# updated_sami_board.net
KiCad netlist of a schematic drawn in Altium Designer
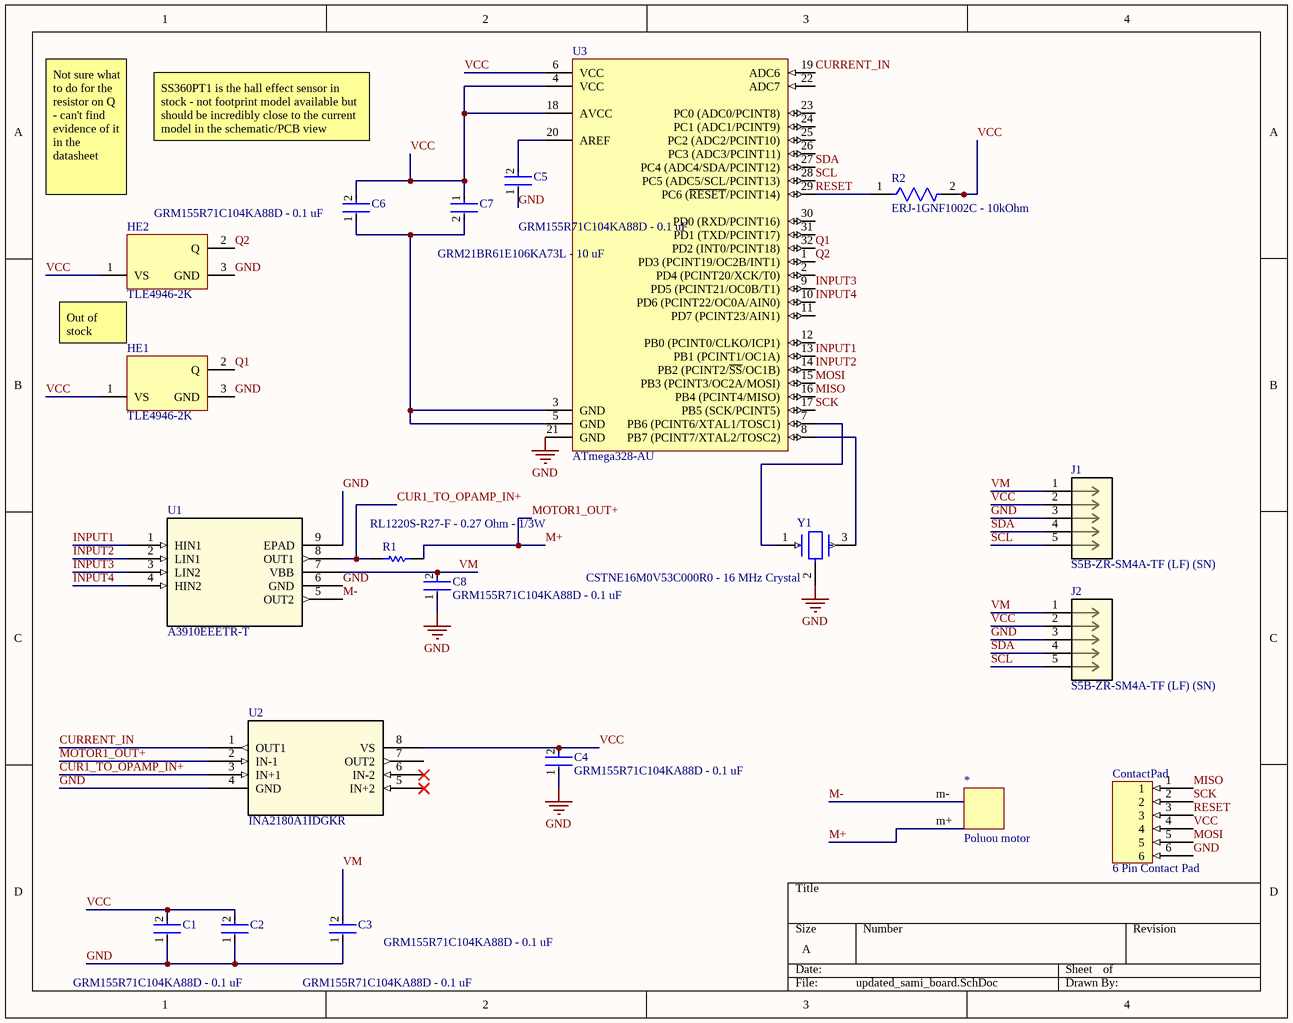
[diagram p0: updated_sami_board.SchDoc]

(export (version "E")
  (design (tool "Eeschema 10.0.6"))
  (components
    (comp (ref "*")
      (value "Poluou motor")
      (footprint "PCBComponent_1")
      (libsource (lib "polulu_motor") (part "Poluou motor"))
    )
    (comp (ref "C1")
      (value "GRM155R71C104KA88D - 0.1 uF")
      (footprint "FP-GRM15-MFG")
      (description "CAP CER 0.1UF 16V X7R 0402")
      (fields (field (name "MANUFACTURER PART NUMBER") "GRM155R71C104KA88D") (field (name "TOLERANCE") "10%"))
      (libsource (lib "Altium Content Vault") (part "236180d848d6139a670b325ea6854c9"))
    )
    (comp (ref "C2")
      (value "GRM155R71C104KA88D - 0.1 uF")
      (footprint "FP-GRM15-MFG")
      (description "CAP CER 0.1UF 16V X7R 0402")
      (fields (field (name "MANUFACTURER PART NUMBER") "GRM155R71C104KA88D") (field (name "TOLERANCE") "10%"))
      (libsource (lib "Altium Content Vault") (part "236180d848d6139a670b325ea6854c9"))
    )
    (comp (ref "C3")
      (value "GRM155R71C104KA88D - 0.1 uF")
      (footprint "FP-GRM15-MFG")
      (description "CAP CER 0.1UF 16V X7R 0402")
      (fields (field (name "MANUFACTURER PART NUMBER") "GRM155R71C104KA88D") (field (name "TOLERANCE") "10%"))
      (libsource (lib "Altium Content Vault") (part "236180d848d6139a670b325ea6854c9"))
    )
    (comp (ref "C4")
      (value "GRM155R71C104KA88D - 0.1 uF")
      (footprint "FP-GRM15-MFG")
      (description "CAP CER 0.1UF 16V X7R 0402")
      (fields (field (name "MANUFACTURER PART NUMBER") "GRM155R71C104KA88D") (field (name "TOLERANCE") "10%"))
      (libsource (lib "Altium Content Vault") (part "236180d848d6139a670b325ea6854c9"))
    )
    (comp (ref "C5")
      (value "GRM155R71C104KA88D - 0.1 uF")
      (footprint "FP-GRM15-MFG")
      (description "CAP CER 0.1UF 16V X7R 0402")
      (fields (field (name "MANUFACTURER PART NUMBER") "GRM155R71C104KA88D") (field (name "TOLERANCE") "10%"))
      (libsource (lib "Altium Content Vault") (part "236180d848d6139a670b325ea6854c9"))
    )
    (comp (ref "C6")
      (value "GRM155R71C104KA88D - 0.1 uF")
      (footprint "FP-GRM15-MFG")
      (description "CAP CER 0.1UF 16V X7R 0402")
      (fields (field (name "MANUFACTURER PART NUMBER") "GRM155R71C104KA88D") (field (name "TOLERANCE") "10%"))
      (libsource (lib "Altium Content Vault") (part "236180d848d6139a670b325ea6854c9"))
    )
    (comp (ref "C7")
      (value "GRM21BR61E106KA73L - 10 uF")
      (footprint "FP-GRM21B-0_15-IPC_C")
      (description "Chip Multilayer Ceramic Capacitors for General Purpose, 0805, 10uF, X5R, 15%, 10%, 25V")
      (fields (field (name "VOLTAGE") "25V") (field (name "TOLERANCE") "10%"))
      (libsource (lib "Altium Content Vault") (part "b4654b650e69147ec39a6b967a45e02"))
    )
    (comp (ref "C8")
      (value "GRM155R71C104KA88D - 0.1 uF")
      (footprint "FP-GRM15-MFG")
      (description "CAP CER 0.1UF 16V X7R 0402")
      (fields (field (name "MANUFACTURER PART NUMBER") "GRM155R71C104KA88D") (field (name "TOLERANCE") "10%"))
      (libsource (lib "Altium Content Vault") (part "236180d848d6139a670b325ea6854c9"))
    )
    (comp (ref "ContactPad")
      (value "6 Pin Contact Pad")
      (footprint "6PinContactPad")
      (libsource (lib "6PinContactPad") (part "6 Pin Contact Pad"))
    )
    (comp (ref "HE1")
      (value "TLE4946-2K")
      (footprint "INF-PG-SC59_M")
      (description "High Precision Hall Effect Latch, PG-SC59, Reel, Green")
      (fields (field (name "MANUFACTURER") "Infineon"))
      (libsource (lib "Altium Content Vault") (part "INF-TLE49XX-SC59-3"))
    )
    (comp (ref "HE2")
      (value "TLE4946-2K")
      (footprint "INF-PG-SC59_M")
      (description "High Precision Hall Effect Latch, PG-SC59, Reel, Green")
      (fields (field (name "MANUFACTURER") "Infineon"))
      (libsource (lib "Altium Content Vault") (part "INF-TLE49XX-SC59-3"))
    )
    (comp (ref "J1")
      (value "S5B-ZR-SM4A-TF (LF) (SN)")
      (footprint "CONN_S5B-ZR-SM4A-TF_JST")
      (description "No Description Available")
      (fields (field (name "COPYRIGHT") "Copyright (C) 2021 Ultra Librarian. All rights reserved."))
      (libsource (lib "S5B-ZR-SM4A-TF_LF__SN_") (part "S5B-ZR-SM4A-TF (LF) (SN)"))
    )
    (comp (ref "J2")
      (value "S5B-ZR-SM4A-TF (LF) (SN)")
      (footprint "CONN_S5B-ZR-SM4A-TF_JST")
      (description "No Description Available")
      (fields (field (name "COPYRIGHT") "Copyright (C) 2021 Ultra Librarian. All rights reserved."))
      (libsource (lib "S5B-ZR-SM4A-TF_LF__SN_") (part "S5B-ZR-SM4A-TF (LF) (SN)"))
    )
    (comp (ref "R1")
      (value "RL1220S-R27-F - 0.27 Ohm - 1/3W")
      (footprint "RESC2013X50X40NL20T20")
      (fields (field (name "PART NUMBER") "RL1220S-R27-F") (field (name "MANUFACTURER") "Susumu"))
      (libsource (lib "Altium Content Vault") (part "RES"))
    )
    (comp (ref "R2")
      (value "ERJ-1GNF1002C - 10kOhm")
      (footprint "FP-ERJ1G-MFG")
      (description "RES SMD 10K OHM 1% 1/20W 0201")
      (fields
        (field (name "MANUFACTURER PART NUMBER") "ERJ-1GNF1002C")
        (field (name "OCTOPART") "https://octopart.com/erj-1gnf1002c-panasonic-55419697")
      )
      (libsource (lib "Altium Content Vault") (part "1029c3af85768c4190bb7ad29bc67b5"))
    )
    (comp (ref "U1")
      (value "A3910EEETR-T")
      (footprint "DFN-8_ALM")
      (description "No Description Available")
      (fields (field (name "COPYRIGHT") "Copyright (C) 2021 Ultra Librarian. All rights reserved."))
      (libsource (lib "A3910EEETR-T") (part "A3910EEETR-T"))
    )
    (comp (ref "U2")
      (value "INA2180A1IDGKR")
      (footprint "DGK8_TEX")
      (description "No Description Available")
      (fields (field (name "COPYRIGHT") "Copyright (C) 2021 Ultra Librarian. All rights reserved."))
      (libsource (lib "INA2180A1IDGKR") (part "INA2180A1IDGKR"))
    )
    (comp (ref "U3")
      (value "ATmega328-AU")
      (footprint "32A_L")
      (libsource (lib "Altium Content Vault") (part "MC-8B-ATM48-SQ32"))
    )
    (comp (ref "Y1")
      (value "CSTNE16M0V53C000R0 - 16 MHz Crystal")
      (footprint "FP-CSTNE16M0V53C000R0-MFG")
      (description "CERAMIC RES 16.0000MHZ 15PF SMD")
      (libsource (lib "Altium Content Vault") (part "7d37667f5012bb31280c8009ddd0b1c"))
    )
  )
  (nets
    (net (code "1") (name "/CUR1_TO_OPAMP_IN+") (class "Default")
      (node (ref "R1") (pin "1") (pinfunction "1_1") (pintype "passive"))
      (node (ref "U1") (pin "8") (pinfunction "OUT1_8") (pintype "output"))
      (node (ref "U2") (pin "3") (pinfunction "IN+1_3") (pintype "input"))
    )
    (net (code "2") (name "/CURRENT_IN") (class "Default")
      (node (ref "U2") (pin "1") (pinfunction "OUT1_1") (pintype "output"))
      (node (ref "U3") (pin "19") (pinfunction "ADC6_19") (pintype "input"))
    )
    (net (code "3") (name "/INPUT1") (class "Default")
      (node (ref "U1") (pin "1") (pinfunction "HIN1_1") (pintype "input"))
      (node (ref "U3") (pin "13") (pinfunction "PB1_(PCINT1/OC1A)_13") (pintype "bidirectional"))
    )
    (net (code "4") (name "/INPUT2") (class "Default")
      (node (ref "U1") (pin "2") (pinfunction "LIN1_2") (pintype "input"))
      (node (ref "U3") (pin "14") (pinfunction "PB2_(PCINT2/~{SS}/OC1B)_14") (pintype "bidirectional"))
    )
    (net (code "5") (name "/INPUT3") (class "Default")
      (node (ref "U1") (pin "3") (pinfunction "LIN2_3") (pintype "input"))
      (node (ref "U3") (pin "9") (pinfunction "PD5_(PCINT21/OC0B/T1)_9") (pintype "bidirectional"))
    )
    (net (code "6") (name "/INPUT4") (class "Default")
      (node (ref "U1") (pin "4") (pinfunction "HIN2_4") (pintype "input"))
      (node (ref "U3") (pin "10") (pinfunction "PD6_(PCINT22/OC0A/AIN0)_10") (pintype "bidirectional"))
    )
    (net (code "7") (name "/M+") (class "Default")
      (node (ref "*") (pin "m+") (pintype "passive"))
      (node (ref "R1") (pin "2") (pinfunction "2_2") (pintype "passive"))
      (node (ref "U2") (pin "2") (pinfunction "IN-1_2") (pintype "input"))
    )
    (net (code "8") (name "/M-") (class "Default")
      (node (ref "*") (pin "m-") (pintype "passive"))
      (node (ref "U1") (pin "5") (pinfunction "OUT2_5") (pintype "output"))
    )
    (net (code "9") (name "/MISO") (class "Default")
      (node (ref "ContactPad") (pin "1") (pinfunction "1_1") (pintype "input"))
      (node (ref "U3") (pin "16") (pinfunction "PB4_(PCINT4/MISO)_16") (pintype "bidirectional"))
    )
    (net (code "10") (name "/MOSI") (class "Default")
      (node (ref "ContactPad") (pin "5") (pinfunction "5_5") (pintype "input"))
      (node (ref "U3") (pin "15") (pinfunction "PB3_(PCINT3/OC2A/MOSI)_15") (pintype "bidirectional"))
    )
    (net (code "11") (name "/Q1") (class "Default")
      (node (ref "HE1") (pin "2") (pinfunction "Q_2") (pintype "open_collector"))
      (node (ref "U3") (pin "32") (pinfunction "PD2_(INT0/PCINT18)_32") (pintype "bidirectional"))
    )
    (net (code "12") (name "/Q2") (class "Default")
      (node (ref "HE2") (pin "2") (pinfunction "Q_2") (pintype "open_collector"))
      (node (ref "U3") (pin "1") (pinfunction "PD3_(PCINT19/OC2B/INT1)_1") (pintype "bidirectional"))
    )
    (net (code "13") (name "/RESET") (class "Default")
      (node (ref "ContactPad") (pin "3") (pinfunction "3_3") (pintype "input"))
      (node (ref "R2") (pin "1") (pinfunction "1_1") (pintype "passive"))
      (node (ref "U3") (pin "29") (pinfunction "PC6_(~{RESET}/PCINT14)_29") (pintype "bidirectional"))
    )
    (net (code "14") (name "/SCK") (class "Default")
      (node (ref "ContactPad") (pin "2") (pinfunction "2_2") (pintype "input"))
      (node (ref "U3") (pin "17") (pinfunction "PB5_(SCK/PCINT5)_17") (pintype "bidirectional"))
    )
    (net (code "15") (name "/SCL") (class "Default")
      (node (ref "J1") (pin "5") (pinfunction "5_5") (pintype "passive"))
      (node (ref "J2") (pin "5") (pinfunction "5_5") (pintype "passive"))
      (node (ref "U3") (pin "28") (pinfunction "PC5_(ADC5/SCL/PCINT13)_28") (pintype "bidirectional"))
    )
    (net (code "16") (name "/SDA") (class "Default")
      (node (ref "J1") (pin "4") (pinfunction "4_4") (pintype "passive"))
      (node (ref "J2") (pin "4") (pinfunction "4_4") (pintype "passive"))
      (node (ref "U3") (pin "27") (pinfunction "PC4_(ADC4/SDA/PCINT12)_27") (pintype "bidirectional"))
    )
    (net (code "17") (name "/VCC") (class "Default")
      (node (ref "C1") (pin "2") (pinfunction "2_2") (pintype "passive"))
      (node (ref "C2") (pin "2") (pinfunction "2_2") (pintype "passive"))
      (node (ref "C4") (pin "2") (pinfunction "2_2") (pintype "passive"))
      (node (ref "C6") (pin "2") (pinfunction "2_2") (pintype "passive"))
      (node (ref "C7") (pin "1") (pinfunction "1_1") (pintype "passive"))
      (node (ref "ContactPad") (pin "4") (pinfunction "4_4") (pintype "input"))
      (node (ref "HE1") (pin "1") (pinfunction "VS_1") (pintype "power_in"))
      (node (ref "HE2") (pin "1") (pinfunction "VS_1") (pintype "power_in"))
      (node (ref "J1") (pin "2") (pinfunction "2_2") (pintype "passive"))
      (node (ref "J2") (pin "2") (pinfunction "2_2") (pintype "passive"))
      (node (ref "R2") (pin "2") (pinfunction "2_2") (pintype "passive"))
      (node (ref "U2") (pin "8") (pinfunction "VS_8") (pintype "power_in"))
      (node (ref "U3") (pin "18") (pinfunction "AVCC_18") (pintype "power_in"))
      (node (ref "U3") (pin "4") (pinfunction "VCC_4") (pintype "power_in"))
      (node (ref "U3") (pin "6") (pinfunction "VCC_6") (pintype "power_in"))
    )
    (net (code "18") (name "/VM") (class "Default")
      (node (ref "C3") (pin "2") (pinfunction "2_2") (pintype "passive"))
      (node (ref "C8") (pin "2") (pinfunction "2_2") (pintype "passive"))
      (node (ref "J1") (pin "1") (pinfunction "1_1") (pintype "passive"))
      (node (ref "J2") (pin "1") (pinfunction "1_1") (pintype "passive"))
      (node (ref "U1") (pin "7") (pinfunction "VBB_7") (pintype "passive"))
    )
    (net (code "19") (name "GND") (class "Default")
      (node (ref "C1") (pin "1") (pinfunction "1_1") (pintype "passive"))
      (node (ref "C2") (pin "1") (pinfunction "1_1") (pintype "passive"))
      (node (ref "C3") (pin "1") (pinfunction "1_1") (pintype "passive"))
      (node (ref "C4") (pin "1") (pinfunction "1_1") (pintype "passive"))
      (node (ref "C5") (pin "1") (pinfunction "1_1") (pintype "passive"))
      (node (ref "C8") (pin "1") (pinfunction "1_1") (pintype "passive"))
      (node (ref "ContactPad") (pin "6") (pinfunction "6_6") (pintype "input"))
      (node (ref "HE1") (pin "3") (pinfunction "GND_3") (pintype "power_in"))
      (node (ref "HE2") (pin "3") (pinfunction "GND_3") (pintype "power_in"))
      (node (ref "J1") (pin "3") (pinfunction "3_3") (pintype "passive"))
      (node (ref "J2") (pin "3") (pinfunction "3_3") (pintype "passive"))
      (node (ref "U1") (pin "6") (pinfunction "GND_6") (pintype "passive"))
      (node (ref "U1") (pin "9") (pinfunction "EPAD_9") (pintype "passive"))
      (node (ref "U2") (pin "4") (pinfunction "GND_4") (pintype "power_in"))
      (node (ref "U3") (pin "21") (pinfunction "GND_21") (pintype "power_in"))
      (node (ref "Y1") (pin "2") (pinfunction "GND_2") (pintype "power_in"))
    )
    (net (code "20") (name "Net-(C6-Pad1)") (class "Default")
      (node (ref "C6") (pin "1") (pinfunction "1_1") (pintype "passive"))
      (node (ref "C7") (pin "2") (pinfunction "2_2") (pintype "passive"))
      (node (ref "U3") (pin "3") (pinfunction "GND_3") (pintype "power_in"))
      (node (ref "U3") (pin "5") (pinfunction "GND_5") (pintype "power_in"))
    )
    (net (code "21") (name "Net-(U3-AREF)") (class "Default")
      (node (ref "C5") (pin "2") (pinfunction "2_2") (pintype "passive"))
      (node (ref "U3") (pin "20") (pinfunction "AREF_20") (pintype "passive"))
    )
    (net (code "22") (name "Net-(U3-PB6_(PCINT6{slash}XTAL1{slash}TOSC1))") (class "Default")
      (node (ref "U3") (pin "7") (pinfunction "PB6_(PCINT6/XTAL1/TOSC1)_7") (pintype "bidirectional"))
      (node (ref "Y1") (pin "1") (pinfunction "Input_1") (pintype "input"))
    )
    (net (code "23") (name "Net-(U3-PB7_(PCINT7{slash}XTAL2{slash}TOSC2))") (class "Default")
      (node (ref "U3") (pin "8") (pinfunction "PB7_(PCINT7/XTAL2/TOSC2)_8") (pintype "bidirectional"))
      (node (ref "Y1") (pin "3") (pinfunction "Output_3") (pintype "output"))
    )
    (net (code "24") (name "unconnected-(U2-IN+2-Pad5)") (class "Default")
      (node (ref "U2") (pin "5") (pinfunction "IN+2_5") (pintype "input+no_connect"))
    )
    (net (code "25") (name "unconnected-(U2-IN-2-Pad6)") (class "Default")
      (node (ref "U2") (pin "6") (pinfunction "IN-2_6") (pintype "input+no_connect"))
    )
    (net (code "26") (name "unconnected-(U2-OUT2-Pad7)") (class "Default")
      (node (ref "U2") (pin "7") (pinfunction "OUT2_7") (pintype "output"))
    )
    (net (code "27") (name "unconnected-(U3-ADC7-Pad22)") (class "Default")
      (node (ref "U3") (pin "22") (pinfunction "ADC7_22") (pintype "input"))
    )
    (net (code "28") (name "unconnected-(U3-PB0_(PCINT0{slash}CLKO{slash}ICP1)-Pad12)") (class "Default")
      (node (ref "U3") (pin "12") (pinfunction "PB0_(PCINT0/CLKO/ICP1)_12") (pintype "bidirectional"))
    )
    (net (code "29") (name "unconnected-(U3-PC0_(ADC0{slash}PCINT8)-Pad23)") (class "Default")
      (node (ref "U3") (pin "23") (pinfunction "PC0_(ADC0/PCINT8)_23") (pintype "bidirectional"))
    )
    (net (code "30") (name "unconnected-(U3-PC1_(ADC1{slash}PCINT9)-Pad24)") (class "Default")
      (node (ref "U3") (pin "24") (pinfunction "PC1_(ADC1/PCINT9)_24") (pintype "bidirectional"))
    )
    (net (code "31") (name "unconnected-(U3-PC2_(ADC2{slash}PCINT10)-Pad25)") (class "Default")
      (node (ref "U3") (pin "25") (pinfunction "PC2_(ADC2/PCINT10)_25") (pintype "bidirectional"))
    )
    (net (code "32") (name "unconnected-(U3-PC3_(ADC3{slash}PCINT11)-Pad26)") (class "Default")
      (node (ref "U3") (pin "26") (pinfunction "PC3_(ADC3/PCINT11)_26") (pintype "bidirectional"))
    )
    (net (code "33") (name "unconnected-(U3-PD0_(RXD{slash}PCINT16)-Pad30)") (class "Default")
      (node (ref "U3") (pin "30") (pinfunction "PD0_(RXD/PCINT16)_30") (pintype "bidirectional"))
    )
    (net (code "34") (name "unconnected-(U3-PD1_(TXD{slash}PCINT17)-Pad31)") (class "Default")
      (node (ref "U3") (pin "31") (pinfunction "PD1_(TXD/PCINT17)_31") (pintype "bidirectional"))
    )
    (net (code "35") (name "unconnected-(U3-PD4_(PCINT20{slash}XCK{slash}T0)-Pad2)") (class "Default")
      (node (ref "U3") (pin "2") (pinfunction "PD4_(PCINT20/XCK/T0)_2") (pintype "bidirectional"))
    )
    (net (code "36") (name "unconnected-(U3-PD7_(PCINT23{slash}AIN1)-Pad11)") (class "Default")
      (node (ref "U3") (pin "11") (pinfunction "PD7_(PCINT23/AIN1)_11") (pintype "bidirectional"))
    )
  )
)
